# powerSwitch.net
KiCad netlist of a schematic drawn in EAGLE
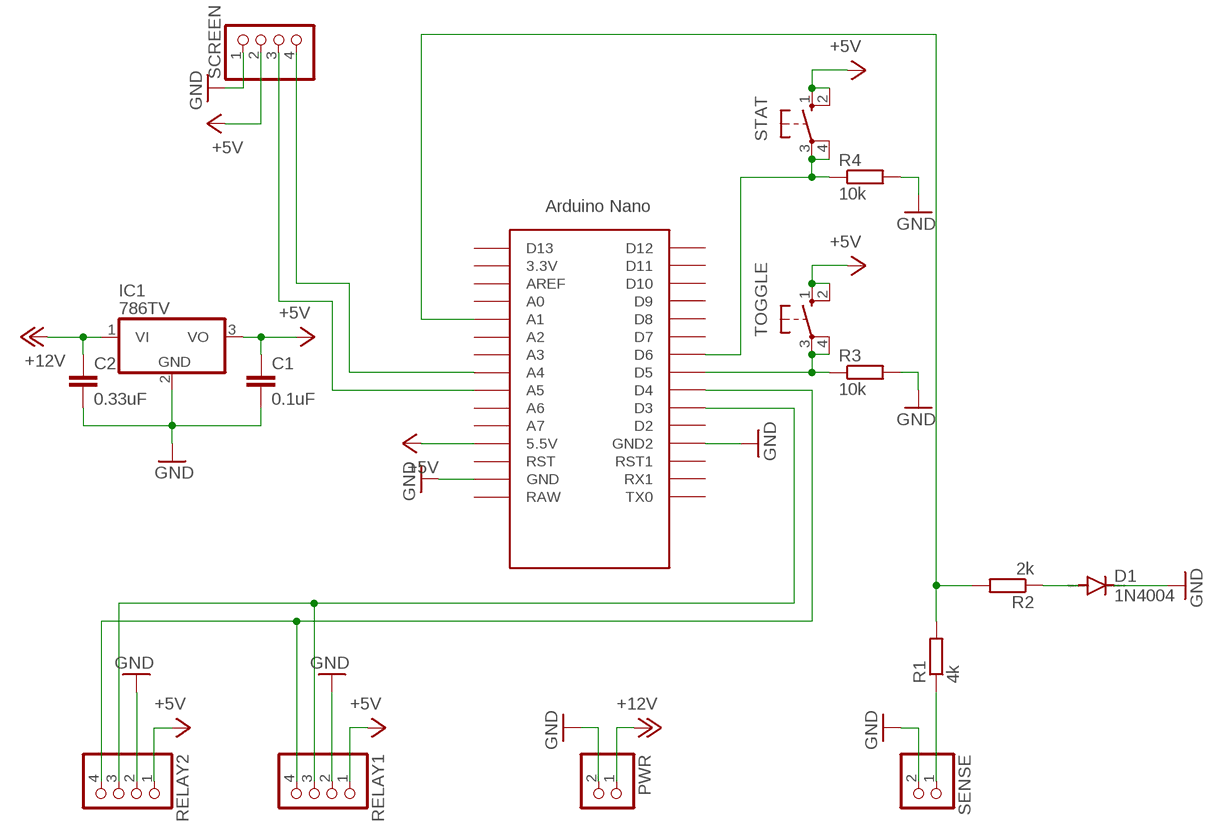
[diagram p0: schematic, sheet 1]

(export (version "E")
  (design (tool "Eeschema 10.0.6"))
  (components
    (comp (ref "C1")
      (value "0.1uF")
      (footprint "eagle-import:C5B2.5")
      (libsource (lib "eagle-import") (part "C5/2.5"))
    )
    (comp (ref "C2")
      (value "0.33uF")
      (footprint "eagle-import:C5B2.5")
      (libsource (lib "eagle-import") (part "C5/2.5"))
    )
    (comp (ref "D1")
      (value "1N4004")
      (footprint "eagle-import:DO41-10")
      (libsource (lib "eagle-import") (part "1N4004"))
    )
    (comp (ref "IC1")
      (value "786TV")
      (footprint "eagle-import:TO220V")
      (libsource (lib "eagle-import") (part "78TV6"))
    )
    (comp (ref "NANO")
      (value "NANO")
      (footprint "eagle-import:NANO")
      (libsource (lib "eagle-import") (part "NANO"))
    )
    (comp (ref "PWR")
      (value "PINHD-1X2")
      (footprint "eagle-import:1X02")
      (libsource (lib "eagle-import") (part "PINHD-1X2"))
    )
    (comp (ref "R1")
      (value "4k")
      (footprint "eagle-import:0204_7")
      (libsource (lib "eagle-import") (part "R-EU_0204/7"))
    )
    (comp (ref "R2")
      (value "2k")
      (footprint "eagle-import:0204_7")
      (libsource (lib "eagle-import") (part "R-EU_0204/7"))
    )
    (comp (ref "R3")
      (value "10k")
      (footprint "eagle-import:0204_7")
      (libsource (lib "eagle-import") (part "R-EU_0204/7"))
    )
    (comp (ref "R4")
      (value "10k")
      (footprint "eagle-import:0204_7")
      (libsource (lib "eagle-import") (part "R-EU_0204/7"))
    )
    (comp (ref "RELAY1")
      (value "PINHD-1X4")
      (footprint "eagle-import:1X04")
      (libsource (lib "eagle-import") (part "PINHD-1X4"))
    )
    (comp (ref "RELAY2")
      (value "PINHD-1X4")
      (footprint "eagle-import:1X04")
      (libsource (lib "eagle-import") (part "PINHD-1X4"))
    )
    (comp (ref "SCREEN")
      (value "PINHD-1X4")
      (footprint "eagle-import:1X04")
      (libsource (lib "eagle-import") (part "PINHD-1X4"))
    )
    (comp (ref "SENSE")
      (value "PINHD-1X2")
      (footprint "eagle-import:1X02")
      (libsource (lib "eagle-import") (part "PINHD-1X2"))
    )
    (comp (ref "STAT")
      (value "10-XX")
      (footprint "eagle-import:B3F-10XX")
      (fields (field (name "MPN") "B3F-1000"))
      (libsource (lib "eagle-import") (part "10-XX"))
    )
    (comp (ref "TOGGLE")
      (value "10-XX")
      (footprint "eagle-import:B3F-10XX")
      (fields (field (name "MPN") "B3F-1000"))
      (libsource (lib "eagle-import") (part "10-XX"))
    )
  )
  (nets
    (net (code "1") (name "+5V") (class "Default")
      (node (ref "C1") (pin "1") (pinfunction "1_1") (pintype "passive"))
      (node (ref "IC1") (pin "3") (pinfunction "VO_3") (pintype "passive"))
      (node (ref "NANO") (pin "5V") (pinfunction "5.5V_5V") (pintype "bidirectional"))
      (node (ref "RELAY1") (pin "1") (pinfunction "1_1") (pintype "passive"))
      (node (ref "RELAY2") (pin "1") (pinfunction "1_1") (pintype "passive"))
      (node (ref "SCREEN") (pin "2") (pinfunction "2_2") (pintype "passive"))
      (node (ref "STAT") (pin "1") (pinfunction "S_1") (pintype "passive"))
      (node (ref "STAT") (pin "2") (pinfunction "S1_2") (pintype "passive"))
      (node (ref "TOGGLE") (pin "1") (pinfunction "S_1") (pintype "passive"))
      (node (ref "TOGGLE") (pin "2") (pinfunction "S1_2") (pintype "passive"))
    )
    (net (code "2") (name "+12V") (class "Default")
      (node (ref "C2") (pin "1") (pinfunction "1_1") (pintype "passive"))
      (node (ref "IC1") (pin "1") (pinfunction "VI_1") (pintype "input"))
      (node (ref "PWR") (pin "1") (pinfunction "1_1") (pintype "passive"))
    )
    (net (code "3") (name "GND") (class "Default")
      (node (ref "C1") (pin "2") (pinfunction "2_2") (pintype "passive"))
      (node (ref "C2") (pin "2") (pinfunction "2_2") (pintype "passive"))
      (node (ref "D1") (pin "C") (pinfunction "C_C") (pintype "passive"))
      (node (ref "IC1") (pin "2") (pinfunction "GND_2") (pintype "passive"))
      (node (ref "NANO") (pin "GND") (pinfunction "GND_GND") (pintype "bidirectional"))
      (node (ref "NANO") (pin "GND1") (pinfunction "GND2_GND1") (pintype "bidirectional"))
      (node (ref "PWR") (pin "2") (pinfunction "2_2") (pintype "passive"))
      (node (ref "R3") (pin "2") (pinfunction "2_2") (pintype "passive"))
      (node (ref "R4") (pin "2") (pinfunction "2_2") (pintype "passive"))
      (node (ref "RELAY1") (pin "2") (pinfunction "2_2") (pintype "passive"))
      (node (ref "RELAY2") (pin "2") (pinfunction "2_2") (pintype "passive"))
      (node (ref "SCREEN") (pin "1") (pinfunction "1_1") (pintype "passive"))
      (node (ref "SENSE") (pin "2") (pinfunction "2_2") (pintype "passive"))
    )
    (net (code "4") (name "Net-(D1-PadA)") (class "Default")
      (node (ref "D1") (pin "A") (pinfunction "A_A") (pintype "passive"))
      (node (ref "R2") (pin "1") (pinfunction "1_1") (pintype "passive"))
    )
    (net (code "5") (name "Net-(NANO-PadA1)") (class "Default")
      (node (ref "NANO") (pin "A1") (pinfunction "A1_A1") (pintype "bidirectional"))
      (node (ref "R1") (pin "2") (pinfunction "2_2") (pintype "passive"))
      (node (ref "R2") (pin "2") (pinfunction "2_2") (pintype "passive"))
    )
    (net (code "6") (name "Net-(NANO-PadA4)") (class "Default")
      (node (ref "NANO") (pin "A4") (pinfunction "A4_A4") (pintype "bidirectional"))
      (node (ref "SCREEN") (pin "4") (pinfunction "4_4") (pintype "passive"))
    )
    (net (code "7") (name "Net-(NANO-PadA5)") (class "Default")
      (node (ref "NANO") (pin "A5") (pinfunction "A5_A5") (pintype "bidirectional"))
      (node (ref "SCREEN") (pin "3") (pinfunction "3_3") (pintype "passive"))
    )
    (net (code "8") (name "Net-(NANO-PadD3)") (class "Default")
      (node (ref "NANO") (pin "D3") (pinfunction "D3_D3") (pintype "bidirectional"))
      (node (ref "RELAY1") (pin "3") (pinfunction "3_3") (pintype "passive"))
      (node (ref "RELAY2") (pin "3") (pinfunction "3_3") (pintype "passive"))
    )
    (net (code "9") (name "Net-(NANO-PadD4)") (class "Default")
      (node (ref "NANO") (pin "D4") (pinfunction "D4_D4") (pintype "bidirectional"))
      (node (ref "RELAY1") (pin "4") (pinfunction "4_4") (pintype "passive"))
      (node (ref "RELAY2") (pin "4") (pinfunction "4_4") (pintype "passive"))
    )
    (net (code "10") (name "Net-(R1-Pad1)") (class "Default")
      (node (ref "R1") (pin "1") (pinfunction "1_1") (pintype "passive"))
      (node (ref "SENSE") (pin "1") (pinfunction "1_1") (pintype "passive"))
    )
    (net (code "11") (name "Net-(STAT-P)") (class "Default")
      (node (ref "NANO") (pin "D6") (pinfunction "D6_D6") (pintype "bidirectional"))
      (node (ref "R4") (pin "1") (pinfunction "1_1") (pintype "passive"))
      (node (ref "STAT") (pin "3") (pinfunction "P_3") (pintype "passive"))
      (node (ref "STAT") (pin "4") (pinfunction "P1_4") (pintype "passive"))
    )
    (net (code "12") (name "Net-(TOGGLE-P)") (class "Default")
      (node (ref "NANO") (pin "D5") (pinfunction "D5_D5") (pintype "bidirectional"))
      (node (ref "R3") (pin "1") (pinfunction "1_1") (pintype "passive"))
      (node (ref "TOGGLE") (pin "3") (pinfunction "P_3") (pintype "passive"))
      (node (ref "TOGGLE") (pin "4") (pinfunction "P1_4") (pintype "passive"))
    )
    (net (code "13") (name "unconnected-(NANO-Pad3.3V)") (class "Default")
      (node (ref "NANO") (pin "3.3V") (pinfunction "3.3V_3.3V") (pintype "bidirectional"))
    )
    (net (code "14") (name "unconnected-(NANO-PadA0)") (class "Default")
      (node (ref "NANO") (pin "A0") (pinfunction "A0_A0") (pintype "bidirectional"))
    )
    (net (code "15") (name "unconnected-(NANO-PadA2)") (class "Default")
      (node (ref "NANO") (pin "A2") (pinfunction "A2_A2") (pintype "bidirectional"))
    )
    (net (code "16") (name "unconnected-(NANO-PadA3)") (class "Default")
      (node (ref "NANO") (pin "A3") (pinfunction "A3_A3") (pintype "bidirectional"))
    )
    (net (code "17") (name "unconnected-(NANO-PadA6)") (class "Default")
      (node (ref "NANO") (pin "A6") (pinfunction "A6_A6") (pintype "bidirectional"))
    )
    (net (code "18") (name "unconnected-(NANO-PadA7)") (class "Default")
      (node (ref "NANO") (pin "A7") (pinfunction "A7_A7") (pintype "bidirectional"))
    )
    (net (code "19") (name "unconnected-(NANO-PadAREF)") (class "Default")
      (node (ref "NANO") (pin "AREF") (pinfunction "AREF_AREF") (pintype "bidirectional"))
    )
    (net (code "20") (name "unconnected-(NANO-PadD2)") (class "Default")
      (node (ref "NANO") (pin "D2") (pinfunction "D2_D2") (pintype "bidirectional"))
    )
    (net (code "21") (name "unconnected-(NANO-PadD7)") (class "Default")
      (node (ref "NANO") (pin "D7") (pinfunction "D7_D7") (pintype "bidirectional"))
    )
    (net (code "22") (name "unconnected-(NANO-PadD8)") (class "Default")
      (node (ref "NANO") (pin "D8") (pinfunction "D8_D8") (pintype "bidirectional"))
    )
    (net (code "23") (name "unconnected-(NANO-PadD9)") (class "Default")
      (node (ref "NANO") (pin "D9") (pinfunction "D9_D9") (pintype "bidirectional"))
    )
    (net (code "24") (name "unconnected-(NANO-PadD10)") (class "Default")
      (node (ref "NANO") (pin "D10") (pinfunction "D10_D10") (pintype "bidirectional"))
    )
    (net (code "25") (name "unconnected-(NANO-PadD11)") (class "Default")
      (node (ref "NANO") (pin "D11") (pinfunction "D11_D11") (pintype "bidirectional"))
    )
    (net (code "26") (name "unconnected-(NANO-PadD12)") (class "Default")
      (node (ref "NANO") (pin "D12") (pinfunction "D12_D12") (pintype "bidirectional"))
    )
    (net (code "27") (name "unconnected-(NANO-PadD13)") (class "Default")
      (node (ref "NANO") (pin "D13") (pinfunction "D13_D13") (pintype "bidirectional"))
    )
    (net (code "28") (name "unconnected-(NANO-PadICSP1)") (class "Default")
      (node (ref "NANO") (pin "ICSP1") (pinfunction "ICSP1_ICSP1") (pintype "bidirectional"))
    )
    (net (code "29") (name "unconnected-(NANO-PadICSP2)") (class "Default")
      (node (ref "NANO") (pin "ICSP2") (pinfunction "ICSP2_ICSP2") (pintype "bidirectional"))
    )
    (net (code "30") (name "unconnected-(NANO-PadICSP3)") (class "Default")
      (node (ref "NANO") (pin "ICSP3") (pinfunction "ICSP3_ICSP3") (pintype "bidirectional"))
    )
    (net (code "31") (name "unconnected-(NANO-PadICSP4)") (class "Default")
      (node (ref "NANO") (pin "ICSP4") (pinfunction "ICSP4_ICSP4") (pintype "bidirectional"))
    )
    (net (code "32") (name "unconnected-(NANO-PadICSP5)") (class "Default")
      (node (ref "NANO") (pin "ICSP5") (pinfunction "ICSP5_ICSP5") (pintype "bidirectional"))
    )
    (net (code "33") (name "unconnected-(NANO-PadICSP6)") (class "Default")
      (node (ref "NANO") (pin "ICSP6") (pinfunction "ICSP6_ICSP6") (pintype "bidirectional"))
    )
    (net (code "34") (name "unconnected-(NANO-PadRAW)") (class "Default")
      (node (ref "NANO") (pin "RAW") (pinfunction "RAW_RAW") (pintype "bidirectional"))
    )
    (net (code "35") (name "unconnected-(NANO-PadRST)") (class "Default")
      (node (ref "NANO") (pin "RST") (pinfunction "RST_RST") (pintype "bidirectional"))
    )
    (net (code "36") (name "unconnected-(NANO-PadRST1)") (class "Default")
      (node (ref "NANO") (pin "RST1") (pinfunction "RST1_RST1") (pintype "bidirectional"))
    )
    (net (code "37") (name "unconnected-(NANO-PadRX1)") (class "Default")
      (node (ref "NANO") (pin "RX1") (pinfunction "RX1_RX1") (pintype "bidirectional"))
    )
    (net (code "38") (name "unconnected-(NANO-PadTX0)") (class "Default")
      (node (ref "NANO") (pin "TX0") (pinfunction "TX0_TX0") (pintype "bidirectional"))
    )
  )
)
